# LDO.net
KiCad netlist of a schematic drawn in Altium Designer
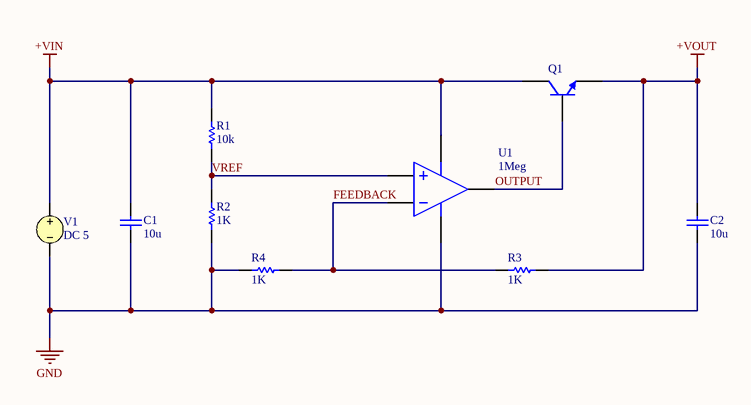
[diagram p0: LDO.SchDoc]

(export (version "E")
  (design (tool "Eeschema 10.0.6"))
  (components
    (comp (ref "C1")
      (value "10u")
      (description "Capacitor")
      (libsource (lib "Simulation Generic Components") (part "Capacitor"))
    )
    (comp (ref "C2")
      (value "10u")
      (description "Capacitor")
      (libsource (lib "Simulation Generic Components") (part "Capacitor"))
    )
    (comp (ref "Q1")
      (value "Bipolar NPN 3 Pins Transistor Modified Version of the Gummel-Poon Model")
      (libsource (lib "Simulation Generic Components") (part "BJT NPN_MGP"))
    )
    (comp (ref "R1")
      (value "10k")
      (description "Resistor")
      (libsource (lib "Simulation Generic Components") (part "Resistor"))
    )
    (comp (ref "R2")
      (value "1K")
      (description "Resistor")
      (libsource (lib "Simulation Generic Components") (part "Resistor"))
    )
    (comp (ref "R3")
      (value "1K")
      (description "Resistor")
      (libsource (lib "Simulation Generic Components") (part "Resistor"))
    )
    (comp (ref "R4")
      (value "1K")
      (description "Resistor")
      (libsource (lib "Simulation Generic Components") (part "Resistor"))
    )
    (comp (ref "U1")
      (value "Ideal Operational Amplifier")
      (fields (field (name "GAIN") "1Meg"))
      (libsource (lib "Simulation Generic Components") (part "OpAmp with power terminals"))
    )
    (comp (ref "V1")
      (value "DC 5")
      (description "Voltage Source")
      (fields (field (name "PUBLISHER") "Altium Limited"))
      (libsource (lib "Simulation Generic Components") (part "VSRC"))
    )
  )
  (nets
    (net (code "1") (name "+VIN") (class "Default")
      (node (ref "C1") (pin "2") (pinfunction "2_2") (pintype "passive"))
      (node (ref "Q1") (pin "1") (pinfunction "C_1") (pintype "passive"))
      (node (ref "R1") (pin "2") (pinfunction "2_2") (pintype "passive"))
      (node (ref "U1") (pin "5") (pinfunction "V-_5") (pintype "power_in"))
      (node (ref "V1") (pin "1") (pinfunction "1_1") (pintype "passive"))
    )
    (net (code "2") (name "+VOUT") (class "Default")
      (node (ref "C2") (pin "2") (pinfunction "2_2") (pintype "passive"))
      (node (ref "Q1") (pin "3") (pinfunction "E_3") (pintype "passive"))
      (node (ref "R3") (pin "1") (pinfunction "1_1") (pintype "passive"))
    )
    (net (code "3") (name "/FEEDBACK") (class "Default")
      (node (ref "R3") (pin "2") (pinfunction "2_2") (pintype "passive"))
      (node (ref "R4") (pin "1") (pinfunction "1_1") (pintype "passive"))
      (node (ref "U1") (pin "1") (pinfunction "IN-_1") (pintype "passive"))
    )
    (net (code "4") (name "/OUTPUT") (class "Default")
      (node (ref "Q1") (pin "2") (pinfunction "B_2") (pintype "passive"))
      (node (ref "U1") (pin "3") (pinfunction "OUT_3") (pintype "passive"))
    )
    (net (code "5") (name "/VREF") (class "Default")
      (node (ref "R1") (pin "1") (pinfunction "1_1") (pintype "passive"))
      (node (ref "R2") (pin "2") (pinfunction "2_2") (pintype "passive"))
      (node (ref "U1") (pin "2") (pinfunction "IN+_2") (pintype "passive"))
    )
    (net (code "6") (name "GND") (class "Default")
      (node (ref "C1") (pin "1") (pinfunction "1_1") (pintype "passive"))
      (node (ref "C2") (pin "1") (pinfunction "1_1") (pintype "passive"))
      (node (ref "R2") (pin "1") (pinfunction "1_1") (pintype "passive"))
      (node (ref "R4") (pin "2") (pinfunction "2_2") (pintype "passive"))
      (node (ref "U1") (pin "4") (pinfunction "V+_4") (pintype "power_in"))
      (node (ref "V1") (pin "2") (pinfunction "2_2") (pintype "passive"))
    )
  )
)
